# DSPLIT_v0_2.net
KiCad netlist of a schematic drawn in EAGLE
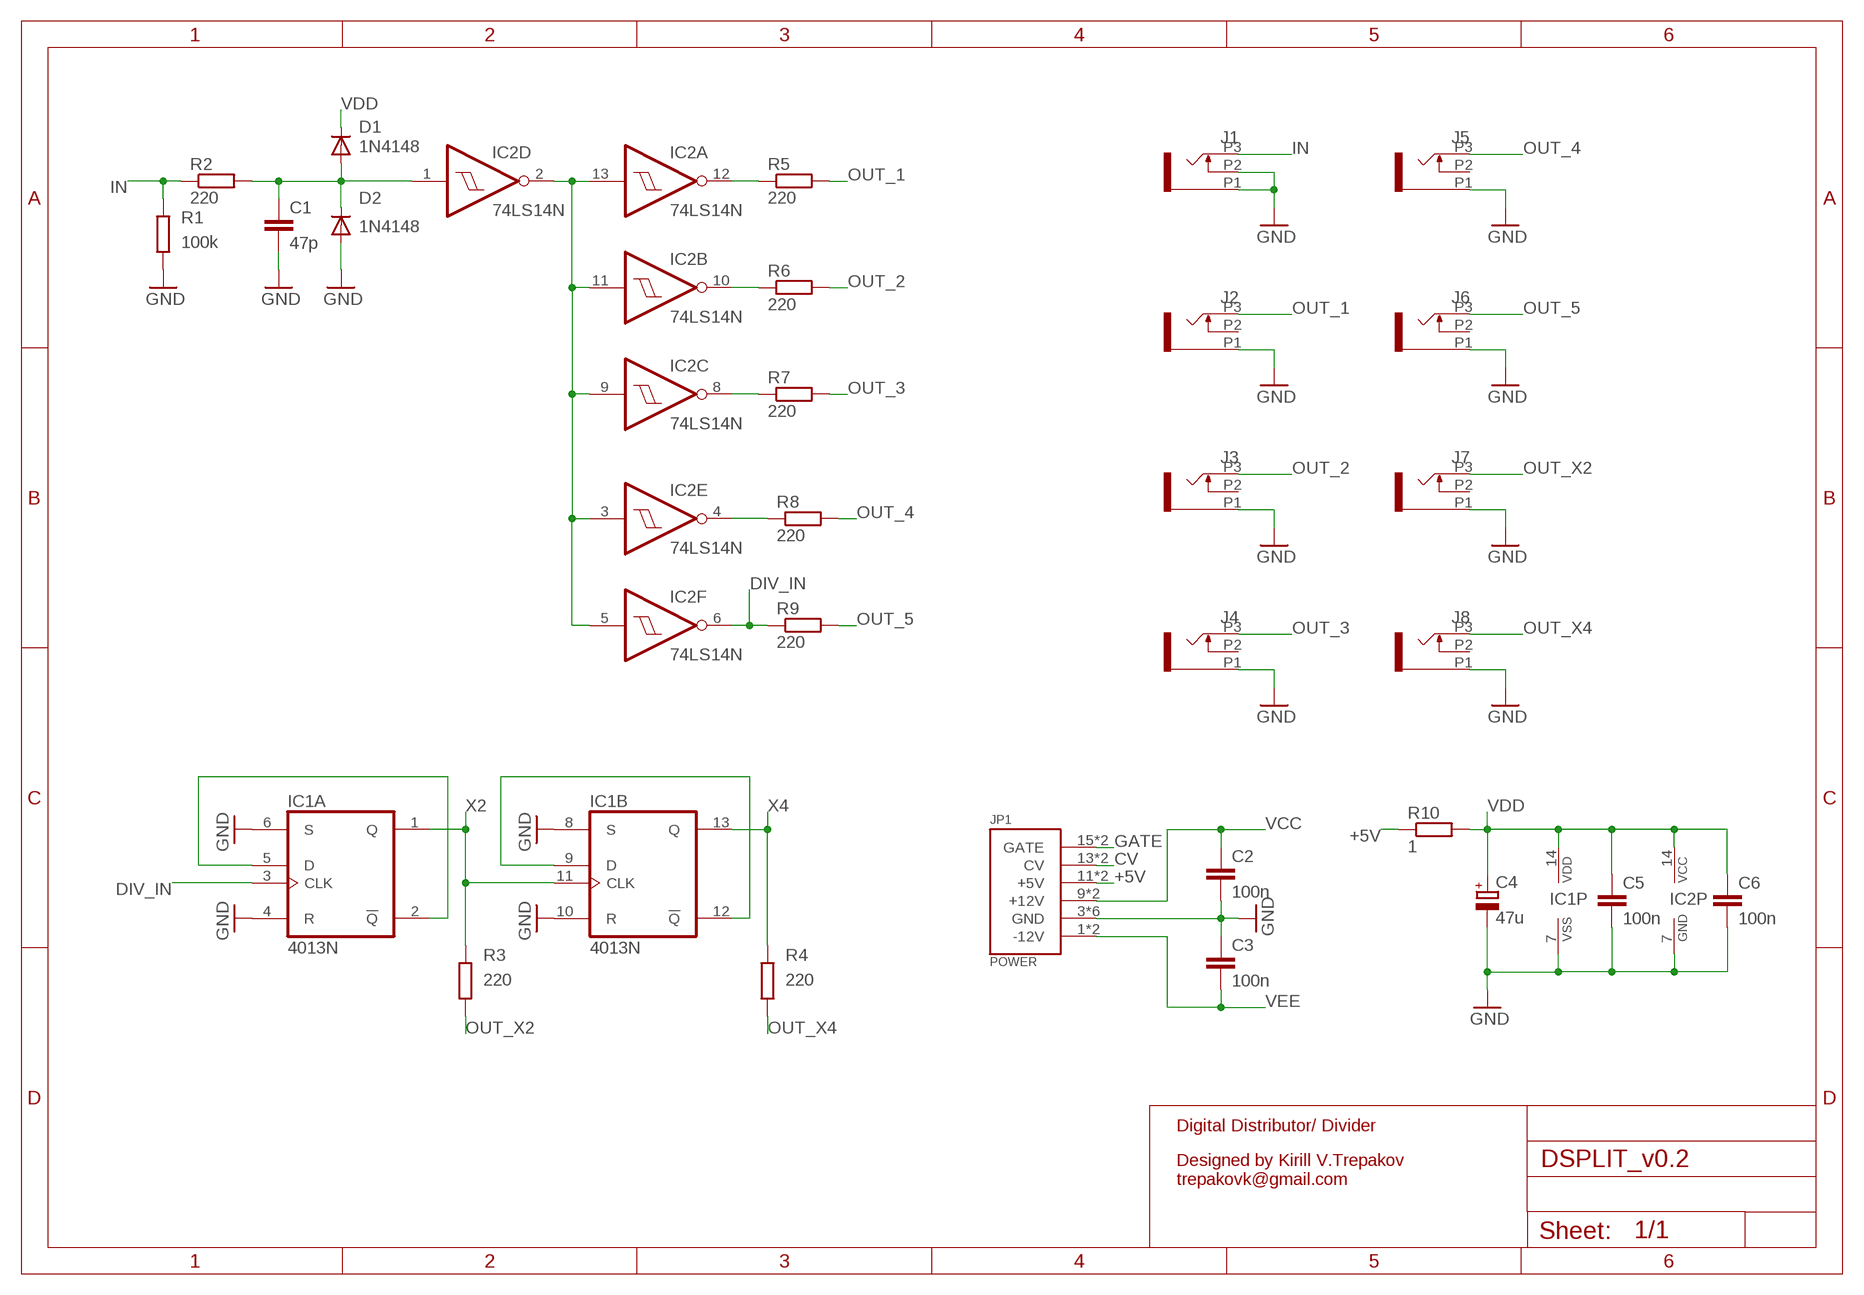
[diagram p0: schematic, sheet 1]

(export (version "E")
  (design (tool "Eeschema 10.0.6"))
  (components
    (comp (ref "C1")
      (value "47p")
      (footprint "eagle-import:C050-024X044")
      (libsource (lib "eagle-import") (part "C-EU050-024X044"))
    )
    (comp (ref "C2")
      (value "100n")
      (footprint "eagle-import:C050-024X044")
      (libsource (lib "eagle-import") (part "C-EU050-024X044"))
    )
    (comp (ref "C3")
      (value "100n")
      (footprint "eagle-import:C050-024X044")
      (libsource (lib "eagle-import") (part "C-EU050-024X044"))
    )
    (comp (ref "C4")
      (value "47u")
      (footprint "eagle-import:E2,5-6")
      (libsource (lib "eagle-import") (part "CPOL-EUE2.5-6"))
    )
    (comp (ref "C5")
      (value "100n")
      (footprint "eagle-import:C050-024X044")
      (libsource (lib "eagle-import") (part "C-EU050-024X044"))
    )
    (comp (ref "C6")
      (value "100n")
      (footprint "eagle-import:C050-024X044")
      (libsource (lib "eagle-import") (part "C-EU050-024X044"))
    )
    (comp (ref "D1")
      (value "1N4148")
      (footprint "eagle-import:DO35-7")
      (libsource (lib "eagle-import") (part "1N4148DO35-7"))
    )
    (comp (ref "D2")
      (value "1N4148")
      (footprint "eagle-import:DO35-7")
      (libsource (lib "eagle-import") (part "1N4148DO35-7"))
    )
    (comp (ref "IC1")
      (value "4013N")
      (footprint "eagle-import:DIL14")
      (libsource (lib "eagle-import") (part "4013N"))
    )
    (comp (ref "IC2")
      (value "74LS14N")
      (footprint "eagle-import:DIL14")
      (libsource (lib "eagle-import") (part "7414NLS"))
    )
    (comp (ref "J1")
      (value "WQP-PJ302M_JACK")
      (footprint "eagle-import:WQP-PJ302M_JACK")
      (libsource (lib "eagle-import") (part "WQP-PJ302M_JACK"))
    )
    (comp (ref "J2")
      (value "WQP-PJ302M_JACK")
      (footprint "eagle-import:WQP-PJ302M_JACK")
      (libsource (lib "eagle-import") (part "WQP-PJ302M_JACK"))
    )
    (comp (ref "J3")
      (value "WQP-PJ302M_JACK")
      (footprint "eagle-import:WQP-PJ302M_JACK")
      (libsource (lib "eagle-import") (part "WQP-PJ302M_JACK"))
    )
    (comp (ref "J4")
      (value "WQP-PJ302M_JACK")
      (footprint "eagle-import:WQP-PJ302M_JACK")
      (libsource (lib "eagle-import") (part "WQP-PJ302M_JACK"))
    )
    (comp (ref "J5")
      (value "WQP-PJ302M_JACK")
      (footprint "eagle-import:WQP-PJ302M_JACK")
      (libsource (lib "eagle-import") (part "WQP-PJ302M_JACK"))
    )
    (comp (ref "J6")
      (value "WQP-PJ302M_JACK")
      (footprint "eagle-import:WQP-PJ302M_JACK")
      (libsource (lib "eagle-import") (part "WQP-PJ302M_JACK"))
    )
    (comp (ref "J7")
      (value "WQP-PJ302M_JACK")
      (footprint "eagle-import:WQP-PJ302M_JACK")
      (libsource (lib "eagle-import") (part "WQP-PJ302M_JACK"))
    )
    (comp (ref "J8")
      (value "WQP-PJ302M_JACK")
      (footprint "eagle-import:WQP-PJ302M_JACK")
      (libsource (lib "eagle-import") (part "WQP-PJ302M_JACK"))
    )
    (comp (ref "JP1")
      (value "POWER")
      (footprint "eagle-import:POWER_16")
      (libsource (lib "eagle-import") (part "POWER{dblquote}"))
    )
    (comp (ref "R1")
      (value "100k")
      (footprint "eagle-import:0204_7")
      (libsource (lib "eagle-import") (part "R-EU_0204/7"))
    )
    (comp (ref "R2")
      (value "220")
      (footprint "eagle-import:0204_7")
      (libsource (lib "eagle-import") (part "R-EU_0204/7"))
    )
    (comp (ref "R3")
      (value "220")
      (footprint "eagle-import:0204_7")
      (libsource (lib "eagle-import") (part "R-EU_0204/7"))
    )
    (comp (ref "R4")
      (value "220")
      (footprint "eagle-import:0204_7")
      (libsource (lib "eagle-import") (part "R-EU_0204/7"))
    )
    (comp (ref "R5")
      (value "220")
      (footprint "eagle-import:0204_7")
      (libsource (lib "eagle-import") (part "R-EU_0204/7"))
    )
    (comp (ref "R6")
      (value "220")
      (footprint "eagle-import:0204_7")
      (libsource (lib "eagle-import") (part "R-EU_0204/7"))
    )
    (comp (ref "R7")
      (value "220")
      (footprint "eagle-import:0204_7")
      (libsource (lib "eagle-import") (part "R-EU_0204/7"))
    )
    (comp (ref "R8")
      (value "220")
      (footprint "eagle-import:0204_7")
      (libsource (lib "eagle-import") (part "R-EU_0204/7"))
    )
    (comp (ref "R9")
      (value "220")
      (footprint "eagle-import:0204_7")
      (libsource (lib "eagle-import") (part "R-EU_0204/7"))
    )
    (comp (ref "R10")
      (value "1")
      (footprint "eagle-import:0204_7")
      (libsource (lib "eagle-import") (part "R-EU_0204/7"))
    )
  )
  (nets
    (net (code "1") (name "/+5V") (class "Default")
      (node (ref "JP1") (pin "11") (pinfunction "+5V_11") (pintype "bidirectional"))
      (node (ref "JP1") (pin "12") (pinfunction "+5V_12") (pintype "bidirectional"))
      (node (ref "R10") (pin "1") (pinfunction "1_1") (pintype "passive"))
    )
    (net (code "2") (name "/CV") (class "Default")
      (node (ref "JP1") (pin "13") (pinfunction "CV_13") (pintype "bidirectional"))
      (node (ref "JP1") (pin "14") (pinfunction "CV_14") (pintype "bidirectional"))
    )
    (net (code "3") (name "/DIV_IN") (class "Default")
      (node (ref "IC1") (pin "3") (pinfunction "CLK_3") (pintype "input"))
      (node (ref "IC2") (pin "6") (pinfunction "O_6") (pintype "output"))
      (node (ref "R9") (pin "1") (pinfunction "1_1") (pintype "passive"))
    )
    (net (code "4") (name "/GATE") (class "Default")
      (node (ref "JP1") (pin "15") (pinfunction "GATE_15") (pintype "bidirectional"))
      (node (ref "JP1") (pin "16") (pinfunction "GATE_16") (pintype "bidirectional"))
    )
    (net (code "5") (name "/IN") (class "Default")
      (node (ref "J1") (pin "P3") (pinfunction "3_P3") (pintype "passive"))
      (node (ref "R1") (pin "2") (pinfunction "2_2") (pintype "passive"))
      (node (ref "R2") (pin "1") (pinfunction "1_1") (pintype "passive"))
    )
    (net (code "6") (name "/OUT_1") (class "Default")
      (node (ref "J2") (pin "P3") (pinfunction "3_P3") (pintype "passive"))
      (node (ref "R5") (pin "2") (pinfunction "2_2") (pintype "passive"))
    )
    (net (code "7") (name "/OUT_2") (class "Default")
      (node (ref "J3") (pin "P3") (pinfunction "3_P3") (pintype "passive"))
      (node (ref "R6") (pin "2") (pinfunction "2_2") (pintype "passive"))
    )
    (net (code "8") (name "/OUT_3") (class "Default")
      (node (ref "J4") (pin "P3") (pinfunction "3_P3") (pintype "passive"))
      (node (ref "R7") (pin "2") (pinfunction "2_2") (pintype "passive"))
    )
    (net (code "9") (name "/OUT_4") (class "Default")
      (node (ref "J5") (pin "P3") (pinfunction "3_P3") (pintype "passive"))
      (node (ref "R8") (pin "2") (pinfunction "2_2") (pintype "passive"))
    )
    (net (code "10") (name "/OUT_5") (class "Default")
      (node (ref "J6") (pin "P3") (pinfunction "3_P3") (pintype "passive"))
      (node (ref "R9") (pin "2") (pinfunction "2_2") (pintype "passive"))
    )
    (net (code "11") (name "/OUT_X2") (class "Default")
      (node (ref "J7") (pin "P3") (pinfunction "3_P3") (pintype "passive"))
      (node (ref "R3") (pin "2") (pinfunction "2_2") (pintype "passive"))
    )
    (net (code "12") (name "/OUT_X4") (class "Default")
      (node (ref "J8") (pin "P3") (pinfunction "3_P3") (pintype "passive"))
      (node (ref "R4") (pin "2") (pinfunction "2_2") (pintype "passive"))
    )
    (net (code "13") (name "/VCC") (class "Default")
      (node (ref "C2") (pin "1") (pinfunction "1_1") (pintype "passive"))
      (node (ref "JP1") (pin "10") (pinfunction "+12V_10") (pintype "bidirectional"))
      (node (ref "JP1") (pin "9") (pinfunction "+12V_9") (pintype "bidirectional"))
    )
    (net (code "14") (name "/VDD") (class "Default")
      (node (ref "C4") (pin "+") (pinfunction "+_+") (pintype "passive"))
      (node (ref "C5") (pin "1") (pinfunction "1_1") (pintype "passive"))
      (node (ref "C6") (pin "1") (pinfunction "1_1") (pintype "passive"))
      (node (ref "D1") (pin "C") (pinfunction "C_C") (pintype "passive"))
      (node (ref "IC1") (pin "14") (pinfunction "VDD_14") (pintype "power_in"))
      (node (ref "IC2") (pin "14") (pinfunction "VCC_14") (pintype "power_in"))
      (node (ref "R10") (pin "2") (pinfunction "2_2") (pintype "passive"))
    )
    (net (code "15") (name "/VEE") (class "Default")
      (node (ref "C3") (pin "2") (pinfunction "2_2") (pintype "passive"))
      (node (ref "JP1") (pin "1") (pinfunction "-12V_1") (pintype "bidirectional"))
      (node (ref "JP1") (pin "2") (pinfunction "-12V_2") (pintype "bidirectional"))
    )
    (net (code "16") (name "/X2") (class "Default")
      (node (ref "IC1") (pin "1") (pinfunction "Q_1") (pintype "output"))
      (node (ref "IC1") (pin "11") (pinfunction "CLK_11") (pintype "input"))
      (node (ref "R3") (pin "1") (pinfunction "1_1") (pintype "passive"))
    )
    (net (code "17") (name "/X4") (class "Default")
      (node (ref "IC1") (pin "13") (pinfunction "Q_13") (pintype "output"))
      (node (ref "R4") (pin "1") (pinfunction "1_1") (pintype "passive"))
    )
    (net (code "18") (name "GND") (class "Default")
      (node (ref "C1") (pin "2") (pinfunction "2_2") (pintype "passive"))
      (node (ref "C2") (pin "2") (pinfunction "2_2") (pintype "passive"))
      (node (ref "C3") (pin "1") (pinfunction "1_1") (pintype "passive"))
      (node (ref "C4") (pin "-") (pinfunction "-_-") (pintype "passive"))
      (node (ref "C5") (pin "2") (pinfunction "2_2") (pintype "passive"))
      (node (ref "C6") (pin "2") (pinfunction "2_2") (pintype "passive"))
      (node (ref "D2") (pin "A") (pinfunction "A_A") (pintype "passive"))
      (node (ref "IC1") (pin "10") (pinfunction "R_10") (pintype "input"))
      (node (ref "IC1") (pin "4") (pinfunction "R_4") (pintype "input"))
      (node (ref "IC1") (pin "6") (pinfunction "S_6") (pintype "input"))
      (node (ref "IC1") (pin "7") (pinfunction "VSS_7") (pintype "power_in"))
      (node (ref "IC1") (pin "8") (pinfunction "S_8") (pintype "input"))
      (node (ref "IC2") (pin "7") (pinfunction "GND_7") (pintype "power_in"))
      (node (ref "J1") (pin "P1") (pinfunction "1_P1") (pintype "passive"))
      (node (ref "J1") (pin "P2") (pinfunction "2_P2") (pintype "passive"))
      (node (ref "J2") (pin "P1") (pinfunction "1_P1") (pintype "passive"))
      (node (ref "J3") (pin "P1") (pinfunction "1_P1") (pintype "passive"))
      (node (ref "J4") (pin "P1") (pinfunction "1_P1") (pintype "passive"))
      (node (ref "J5") (pin "P1") (pinfunction "1_P1") (pintype "passive"))
      (node (ref "J6") (pin "P1") (pinfunction "1_P1") (pintype "passive"))
      (node (ref "J7") (pin "P1") (pinfunction "1_P1") (pintype "passive"))
      (node (ref "J8") (pin "P1") (pinfunction "1_P1") (pintype "passive"))
      (node (ref "JP1") (pin "3") (pinfunction "GND_3") (pintype "bidirectional"))
      (node (ref "JP1") (pin "4") (pinfunction "GND_4") (pintype "bidirectional"))
      (node (ref "JP1") (pin "5") (pinfunction "GND_5") (pintype "bidirectional"))
      (node (ref "JP1") (pin "6") (pinfunction "GND_6") (pintype "bidirectional"))
      (node (ref "JP1") (pin "7") (pinfunction "GND_7") (pintype "bidirectional"))
      (node (ref "JP1") (pin "8") (pinfunction "GND_8") (pintype "bidirectional"))
      (node (ref "R1") (pin "1") (pinfunction "1_1") (pintype "passive"))
    )
    (net (code "19") (name "Net-(IC1A-D)") (class "Default")
      (node (ref "IC1") (pin "2") (pinfunction "~{Q}_2") (pintype "output"))
      (node (ref "IC1") (pin "5") (pinfunction "D_5") (pintype "input"))
    )
    (net (code "20") (name "Net-(IC1B-D)") (class "Default")
      (node (ref "IC1") (pin "12") (pinfunction "~{Q}_12") (pintype "output"))
      (node (ref "IC1") (pin "9") (pinfunction "D_9") (pintype "input"))
    )
    (net (code "21") (name "Net-(IC2A-I)") (class "Default")
      (node (ref "IC2") (pin "11") (pinfunction "I_11") (pintype "input"))
      (node (ref "IC2") (pin "13") (pinfunction "I_13") (pintype "input"))
      (node (ref "IC2") (pin "2") (pinfunction "O_2") (pintype "output"))
      (node (ref "IC2") (pin "3") (pinfunction "I_3") (pintype "input"))
      (node (ref "IC2") (pin "5") (pinfunction "I_5") (pintype "input"))
      (node (ref "IC2") (pin "9") (pinfunction "I_9") (pintype "input"))
    )
    (net (code "22") (name "Net-(IC2A-O)") (class "Default")
      (node (ref "IC2") (pin "12") (pinfunction "O_12") (pintype "output"))
      (node (ref "R5") (pin "1") (pinfunction "1_1") (pintype "passive"))
    )
    (net (code "23") (name "Net-(IC2B-O)") (class "Default")
      (node (ref "IC2") (pin "10") (pinfunction "O_10") (pintype "output"))
      (node (ref "R6") (pin "1") (pinfunction "1_1") (pintype "passive"))
    )
    (net (code "24") (name "Net-(IC2C-O)") (class "Default")
      (node (ref "IC2") (pin "8") (pinfunction "O_8") (pintype "output"))
      (node (ref "R7") (pin "1") (pinfunction "1_1") (pintype "passive"))
    )
    (net (code "25") (name "Net-(IC2D-I)") (class "Default")
      (node (ref "C1") (pin "1") (pinfunction "1_1") (pintype "passive"))
      (node (ref "D1") (pin "A") (pinfunction "A_A") (pintype "passive"))
      (node (ref "D2") (pin "C") (pinfunction "C_C") (pintype "passive"))
      (node (ref "IC2") (pin "1") (pinfunction "I_1") (pintype "input"))
      (node (ref "R2") (pin "2") (pinfunction "2_2") (pintype "passive"))
    )
    (net (code "26") (name "Net-(IC2E-O)") (class "Default")
      (node (ref "IC2") (pin "4") (pinfunction "O_4") (pintype "output"))
      (node (ref "R8") (pin "1") (pinfunction "1_1") (pintype "passive"))
    )
    (net (code "27") (name "unconnected-(J2-2-PadP2)") (class "Default")
      (node (ref "J2") (pin "P2") (pinfunction "2_P2") (pintype "passive"))
    )
    (net (code "28") (name "unconnected-(J3-2-PadP2)") (class "Default")
      (node (ref "J3") (pin "P2") (pinfunction "2_P2") (pintype "passive"))
    )
    (net (code "29") (name "unconnected-(J4-2-PadP2)") (class "Default")
      (node (ref "J4") (pin "P2") (pinfunction "2_P2") (pintype "passive"))
    )
    (net (code "30") (name "unconnected-(J5-2-PadP2)") (class "Default")
      (node (ref "J5") (pin "P2") (pinfunction "2_P2") (pintype "passive"))
    )
    (net (code "31") (name "unconnected-(J6-2-PadP2)") (class "Default")
      (node (ref "J6") (pin "P2") (pinfunction "2_P2") (pintype "passive"))
    )
    (net (code "32") (name "unconnected-(J7-2-PadP2)") (class "Default")
      (node (ref "J7") (pin "P2") (pinfunction "2_P2") (pintype "passive"))
    )
    (net (code "33") (name "unconnected-(J8-2-PadP2)") (class "Default")
      (node (ref "J8") (pin "P2") (pinfunction "2_P2") (pintype "passive"))
    )
  )
)
